# W076D.net
KiCad netlist of a schematic drawn in EAGLE
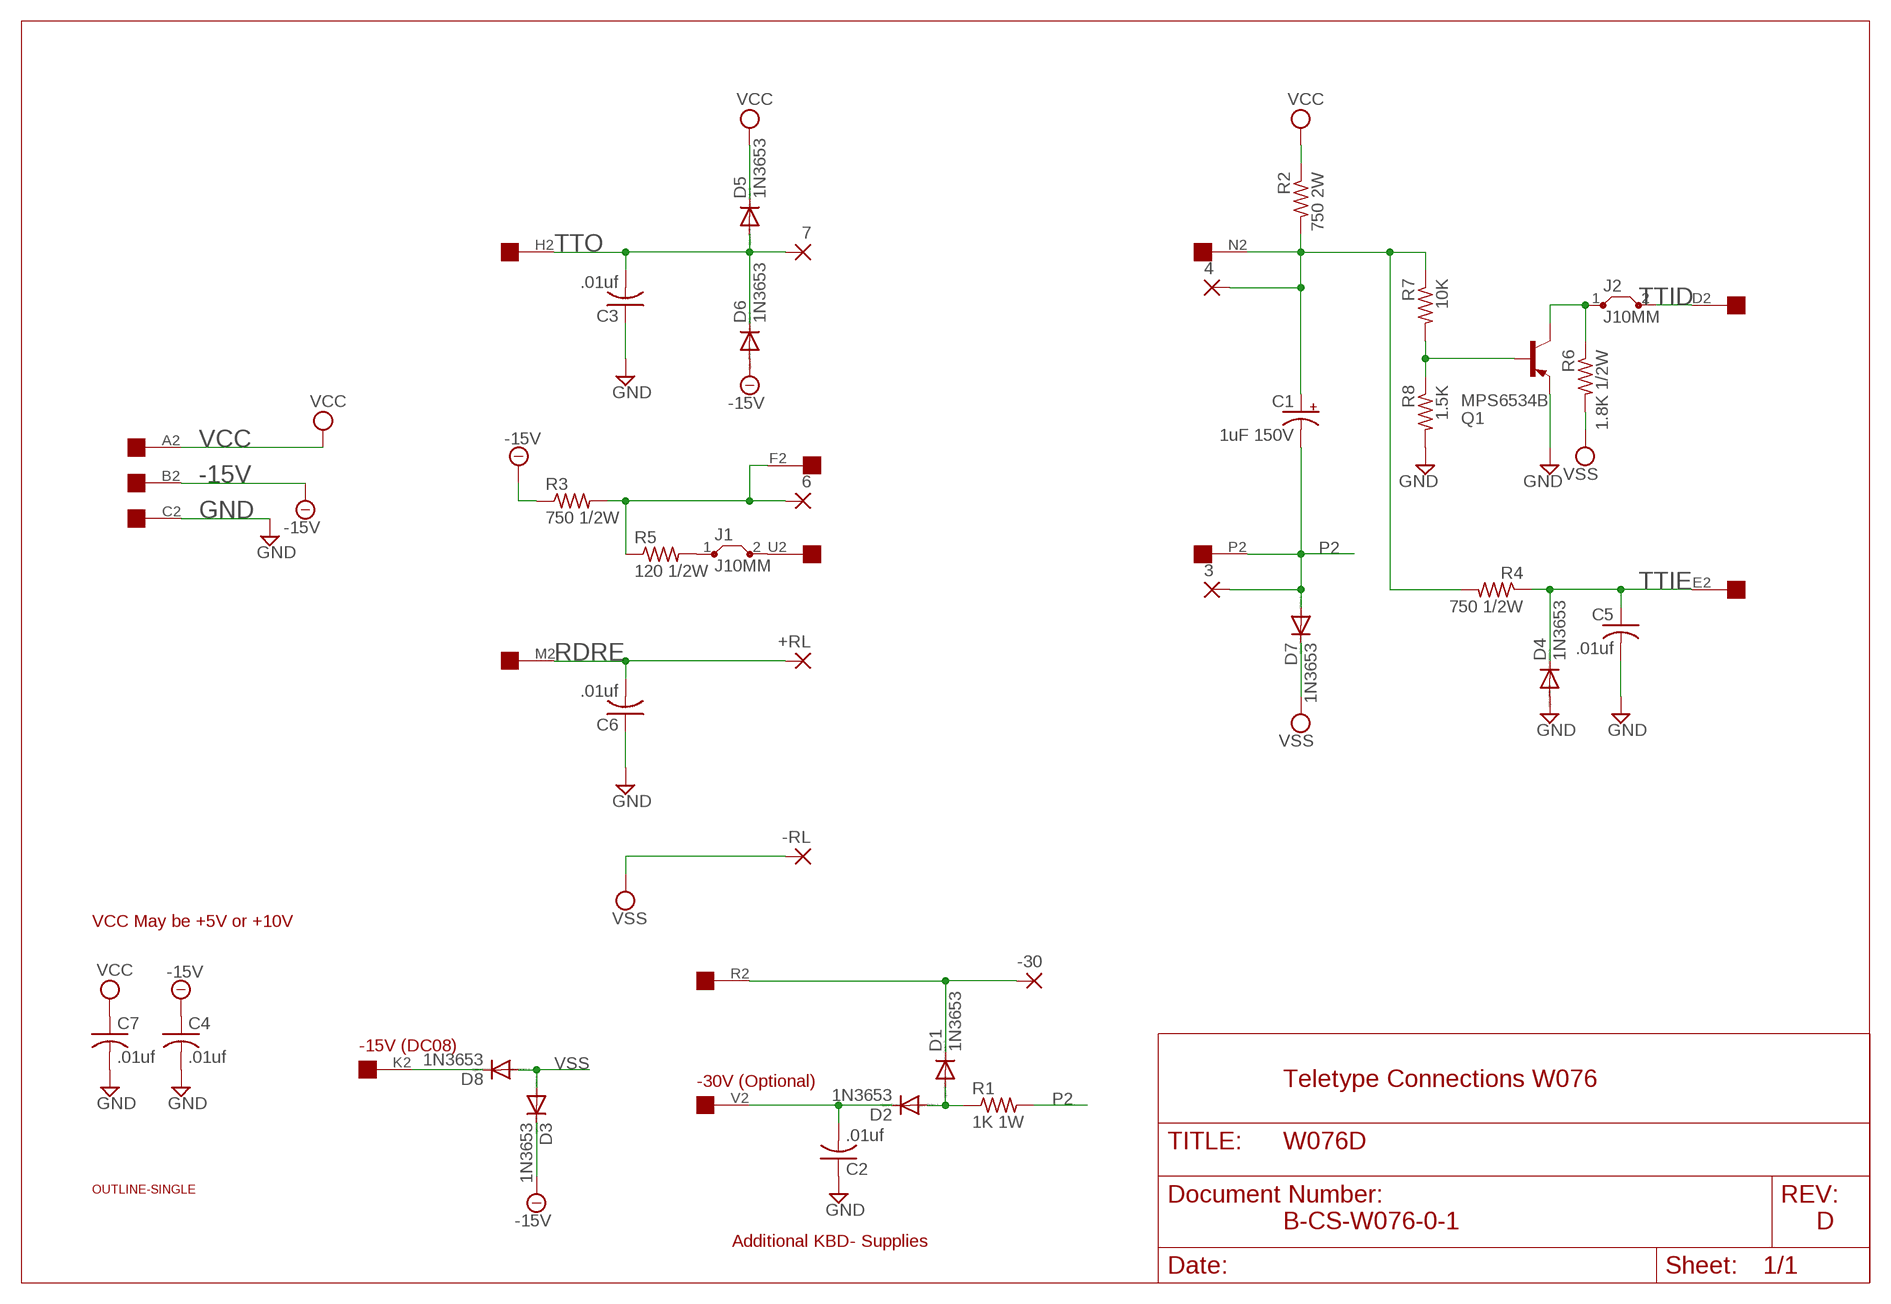
[diagram p0: schematic, sheet 1]

(export (version "E")
  (design (tool "Eeschema 10.0.6"))
  (components
    (comp (ref "+RL")
      (value "2,54/1,0")
      (footprint "eagle-import:2,54_1,0")
      (libsource (lib "eagle-import") (part "2,54/1,0"))
    )
    (comp (ref "-30")
      (value "2,54/1,0")
      (footprint "eagle-import:2,54_1,0")
      (libsource (lib "eagle-import") (part "2,54/1,0"))
    )
    (comp (ref "-RL")
      (value "2,54/1,0")
      (footprint "eagle-import:2,54_1,0")
      (libsource (lib "eagle-import") (part "2,54/1,0"))
    )
    (comp (ref "3")
      (value "2,54/1,0")
      (footprint "eagle-import:2,54_1,0")
      (libsource (lib "eagle-import") (part "2,54/1,0"))
    )
    (comp (ref "4")
      (value "2,54/1,0")
      (footprint "eagle-import:2,54_1,0")
      (libsource (lib "eagle-import") (part "2,54/1,0"))
    )
    (comp (ref "6")
      (value "2,54/1,0")
      (footprint "eagle-import:2,54_1,0")
      (libsource (lib "eagle-import") (part "2,54/1,0"))
    )
    (comp (ref "7")
      (value "2,54/1,0")
      (footprint "eagle-import:2,54_1,0")
      (libsource (lib "eagle-import") (part "2,54/1,0"))
    )
    (comp (ref "C1")
      (value "1uF 150V")
      (footprint "eagle-import:E25-9")
      (libsource (lib "eagle-import") (part "CPOL-USE25-9AXIAL"))
    )
    (comp (ref "C2")
      (value ".01uf")
      (footprint "eagle-import:C050-025X075")
      (libsource (lib "eagle-import") (part "C-US050-025X075"))
    )
    (comp (ref "C3")
      (value ".01uf")
      (footprint "eagle-import:C050-025X075")
      (libsource (lib "eagle-import") (part "C-US050-025X075"))
    )
    (comp (ref "C4")
      (value ".01uf")
      (footprint "eagle-import:C050-025X075")
      (libsource (lib "eagle-import") (part "C-US050-025X075"))
    )
    (comp (ref "C5")
      (value ".01uf")
      (footprint "eagle-import:C050-025X075")
      (libsource (lib "eagle-import") (part "C-US050-025X075"))
    )
    (comp (ref "C6")
      (value ".01uf")
      (footprint "eagle-import:C050-025X075")
      (libsource (lib "eagle-import") (part "C-US050-025X075"))
    )
    (comp (ref "C7")
      (value ".01uf")
      (footprint "eagle-import:C050-025X075")
      (libsource (lib "eagle-import") (part "C-US050-025X075"))
    )
    (comp (ref "D1")
      (value "1N3653")
      (footprint "eagle-import:DO35-10")
      (libsource (lib "eagle-import") (part "1N4148DO35-10"))
    )
    (comp (ref "D2")
      (value "1N3653")
      (footprint "eagle-import:DO35-10")
      (libsource (lib "eagle-import") (part "1N4148DO35-10"))
    )
    (comp (ref "D3")
      (value "1N3653")
      (footprint "eagle-import:DO35-10")
      (libsource (lib "eagle-import") (part "1N4148DO35-10"))
    )
    (comp (ref "D4")
      (value "1N3653")
      (footprint "eagle-import:DO35-10")
      (libsource (lib "eagle-import") (part "1N4148DO35-10"))
    )
    (comp (ref "D5")
      (value "1N3653")
      (footprint "eagle-import:DO35-10")
      (libsource (lib "eagle-import") (part "1N4148DO35-10"))
    )
    (comp (ref "D6")
      (value "1N3653")
      (footprint "eagle-import:DO35-10")
      (libsource (lib "eagle-import") (part "1N4148DO35-10"))
    )
    (comp (ref "D7")
      (value "1N3653")
      (footprint "eagle-import:DO35-10")
      (libsource (lib "eagle-import") (part "1N4148DO35-10"))
    )
    (comp (ref "D8")
      (value "1N3653")
      (footprint "eagle-import:DO35-10")
      (libsource (lib "eagle-import") (part "1N4148DO35-10"))
    )
    (comp (ref "EDGE")
      (value "EDGE-1")
      (footprint "eagle-import:EDGE-CON1")
      (libsource (lib "eagle-import") (part "EDGE-1"))
    )
    (comp (ref "J1")
      (value "J10MM")
      (footprint "eagle-import:10")
      (libsource (lib "eagle-import") (part "J10MM"))
    )
    (comp (ref "J2")
      (value "J10MM")
      (footprint "eagle-import:10")
      (libsource (lib "eagle-import") (part "J10MM"))
    )
    (comp (ref "Q1")
      (value "MPS6534B")
      (footprint "eagle-import:TO39")
      (libsource (lib "eagle-import") (part "2N2904"))
    )
    (comp (ref "R1")
      (value "1K 1W")
      (footprint "eagle-import:P0817_22")
      (libsource (lib "eagle-import") (part "R-US_0817/22"))
    )
    (comp (ref "R2")
      (value "750 2W")
      (footprint "eagle-import:P0817_22")
      (libsource (lib "eagle-import") (part "R-US_0817/22"))
    )
    (comp (ref "R3")
      (value "750 1/2W")
      (footprint "eagle-import:0411_15")
      (libsource (lib "eagle-import") (part "R-US_0411/15"))
    )
    (comp (ref "R4")
      (value "750 1/2W")
      (footprint "eagle-import:0411_15")
      (libsource (lib "eagle-import") (part "R-US_0411/15"))
    )
    (comp (ref "R5")
      (value "120 1/2W")
      (footprint "eagle-import:0411_15")
      (libsource (lib "eagle-import") (part "R-US_0411/15"))
    )
    (comp (ref "R6")
      (value "1.8K 1/2W")
      (footprint "eagle-import:0411_15")
      (libsource (lib "eagle-import") (part "R-US_0411/15"))
    )
    (comp (ref "R7")
      (value "10K")
      (footprint "eagle-import:0207_10")
      (libsource (lib "eagle-import") (part "R-US_0207/10"))
    )
    (comp (ref "R8")
      (value "1.5K")
      (footprint "eagle-import:0207_10")
      (libsource (lib "eagle-import") (part "R-US_0207/10"))
    )
    (comp (ref "U$1")
      (value "OUTLINE-SINGLE")
      (footprint "eagle-import:SINGLE")
      (libsource (lib "eagle-import") (part "OUTLINE-SINGLE"))
    )
  )
  (nets
    (net (code "1") (name "-15V") (class "Default")
      (node (ref "C4") (pin "1") (pinfunction "1_1") (pintype "passive"))
      (node (ref "D3") (pin "C") (pinfunction "C_C") (pintype "passive"))
      (node (ref "D6") (pin "A") (pinfunction "A_A") (pintype "passive"))
      (node (ref "EDGE") (pin "B2") (pinfunction "1_B2") (pintype "bidirectional"))
      (node (ref "R3") (pin "1") (pinfunction "1_1") (pintype "passive"))
    )
    (net (code "2") (name "/P2") (class "Default")
      (node (ref "3") (pin "1") (pinfunction "P_1") (pintype "passive"))
      (node (ref "C1") (pin "-") (pinfunction "-_-") (pintype "passive"))
      (node (ref "D7") (pin "A") (pinfunction "A_A") (pintype "passive"))
      (node (ref "EDGE") (pin "P2") (pinfunction "1_P2") (pintype "bidirectional"))
      (node (ref "R1") (pin "2") (pinfunction "2_2") (pintype "passive"))
    )
    (net (code "3") (name "/RDRE") (class "Default")
      (node (ref "+RL") (pin "1") (pinfunction "P_1") (pintype "passive"))
      (node (ref "C6") (pin "2") (pinfunction "2_2") (pintype "passive"))
      (node (ref "EDGE") (pin "M2") (pinfunction "1_M2") (pintype "bidirectional"))
    )
    (net (code "4") (name "/TTID") (class "Default")
      (node (ref "EDGE") (pin "D2") (pinfunction "1_D2") (pintype "bidirectional"))
      (node (ref "J2") (pin "2") (pinfunction "2_2") (pintype "passive"))
    )
    (net (code "5") (name "/TTIE") (class "Default")
      (node (ref "C5") (pin "1") (pinfunction "1_1") (pintype "passive"))
      (node (ref "D4") (pin "C") (pinfunction "C_C") (pintype "passive"))
      (node (ref "EDGE") (pin "E2") (pinfunction "1_E2") (pintype "bidirectional"))
      (node (ref "R4") (pin "1") (pinfunction "1_1") (pintype "passive"))
    )
    (net (code "6") (name "/TTO") (class "Default")
      (node (ref "7") (pin "1") (pinfunction "P_1") (pintype "passive"))
      (node (ref "C3") (pin "2") (pinfunction "2_2") (pintype "passive"))
      (node (ref "D5") (pin "A") (pinfunction "A_A") (pintype "passive"))
      (node (ref "D6") (pin "C") (pinfunction "C_C") (pintype "passive"))
      (node (ref "EDGE") (pin "H2") (pinfunction "1_H2") (pintype "bidirectional"))
    )
    (net (code "7") (name "GND") (class "Default")
      (node (ref "C2") (pin "1") (pinfunction "1_1") (pintype "passive"))
      (node (ref "C3") (pin "1") (pinfunction "1_1") (pintype "passive"))
      (node (ref "C4") (pin "2") (pinfunction "2_2") (pintype "passive"))
      (node (ref "C5") (pin "2") (pinfunction "2_2") (pintype "passive"))
      (node (ref "C6") (pin "1") (pinfunction "1_1") (pintype "passive"))
      (node (ref "C7") (pin "2") (pinfunction "2_2") (pintype "passive"))
      (node (ref "D4") (pin "A") (pinfunction "A_A") (pintype "passive"))
      (node (ref "EDGE") (pin "C2") (pinfunction "1_C2") (pintype "bidirectional"))
      (node (ref "Q1") (pin "1") (pinfunction "E_1") (pintype "passive"))
      (node (ref "R8") (pin "2") (pinfunction "2_2") (pintype "passive"))
    )
    (net (code "8") (name "Net-(-30-P)") (class "Default")
      (node (ref "-30") (pin "1") (pinfunction "P_1") (pintype "passive"))
      (node (ref "D1") (pin "C") (pinfunction "C_C") (pintype "passive"))
      (node (ref "EDGE") (pin "R2") (pinfunction "1_R2") (pintype "bidirectional"))
    )
    (net (code "9") (name "Net-(4-P)") (class "Default")
      (node (ref "4") (pin "1") (pinfunction "P_1") (pintype "passive"))
      (node (ref "C1") (pin "+") (pinfunction "+_+") (pintype "passive"))
      (node (ref "EDGE") (pin "N2") (pinfunction "1_N2") (pintype "bidirectional"))
      (node (ref "R2") (pin "2") (pinfunction "2_2") (pintype "passive"))
      (node (ref "R4") (pin "2") (pinfunction "2_2") (pintype "passive"))
      (node (ref "R7") (pin "1") (pinfunction "1_1") (pintype "passive"))
    )
    (net (code "10") (name "Net-(6-P)") (class "Default")
      (node (ref "6") (pin "1") (pinfunction "P_1") (pintype "passive"))
      (node (ref "EDGE") (pin "F2") (pinfunction "1_F2") (pintype "bidirectional"))
      (node (ref "R3") (pin "2") (pinfunction "2_2") (pintype "passive"))
      (node (ref "R5") (pin "1") (pinfunction "1_1") (pintype "passive"))
    )
    (net (code "11") (name "Net-(D1-PadA)") (class "Default")
      (node (ref "D1") (pin "A") (pinfunction "A_A") (pintype "passive"))
      (node (ref "D2") (pin "A") (pinfunction "A_A") (pintype "passive"))
      (node (ref "R1") (pin "1") (pinfunction "1_1") (pintype "passive"))
    )
    (net (code "12") (name "Net-(EDGEI-1)") (class "Default")
      (node (ref "D8") (pin "C") (pinfunction "C_C") (pintype "passive"))
      (node (ref "EDGE") (pin "K2") (pinfunction "1_K2") (pintype "bidirectional"))
    )
    (net (code "13") (name "Net-(EDGEQ-1)") (class "Default")
      (node (ref "EDGE") (pin "U2") (pinfunction "1_U2") (pintype "bidirectional"))
      (node (ref "J1") (pin "2") (pinfunction "2_2") (pintype "passive"))
    )
    (net (code "14") (name "Net-(EDGER-1)") (class "Default")
      (node (ref "C2") (pin "2") (pinfunction "2_2") (pintype "passive"))
      (node (ref "D2") (pin "C") (pinfunction "C_C") (pintype "passive"))
      (node (ref "EDGE") (pin "V2") (pinfunction "1_V2") (pintype "bidirectional"))
    )
    (net (code "15") (name "Net-(J1-Pad1)") (class "Default")
      (node (ref "J1") (pin "1") (pinfunction "1_1") (pintype "passive"))
      (node (ref "R5") (pin "2") (pinfunction "2_2") (pintype "passive"))
    )
    (net (code "16") (name "Net-(Q1-B)") (class "Default")
      (node (ref "Q1") (pin "2") (pinfunction "B_2") (pintype "passive"))
      (node (ref "R7") (pin "2") (pinfunction "2_2") (pintype "passive"))
      (node (ref "R8") (pin "1") (pinfunction "1_1") (pintype "passive"))
    )
    (net (code "17") (name "Net-(Q1-C)") (class "Default")
      (node (ref "J2") (pin "1") (pinfunction "1_1") (pintype "passive"))
      (node (ref "Q1") (pin "3") (pinfunction "C_3") (pintype "passive"))
      (node (ref "R6") (pin "1") (pinfunction "1_1") (pintype "passive"))
    )
    (net (code "18") (name "VCC") (class "Default")
      (node (ref "C7") (pin "1") (pinfunction "1_1") (pintype "passive"))
      (node (ref "D5") (pin "C") (pinfunction "C_C") (pintype "passive"))
      (node (ref "EDGE") (pin "A2") (pinfunction "1_A2") (pintype "bidirectional"))
      (node (ref "R2") (pin "1") (pinfunction "1_1") (pintype "passive"))
    )
    (net (code "19") (name "VSS") (class "Default")
      (node (ref "-RL") (pin "1") (pinfunction "P_1") (pintype "passive"))
      (node (ref "D3") (pin "A") (pinfunction "A_A") (pintype "passive"))
      (node (ref "D7") (pin "C") (pinfunction "C_C") (pintype "passive"))
      (node (ref "D8") (pin "A") (pinfunction "A_A") (pintype "passive"))
      (node (ref "R6") (pin "2") (pinfunction "2_2") (pintype "passive"))
    )
  )
)
